# mkii.net
KiCad netlist of a schematic drawn in EAGLE
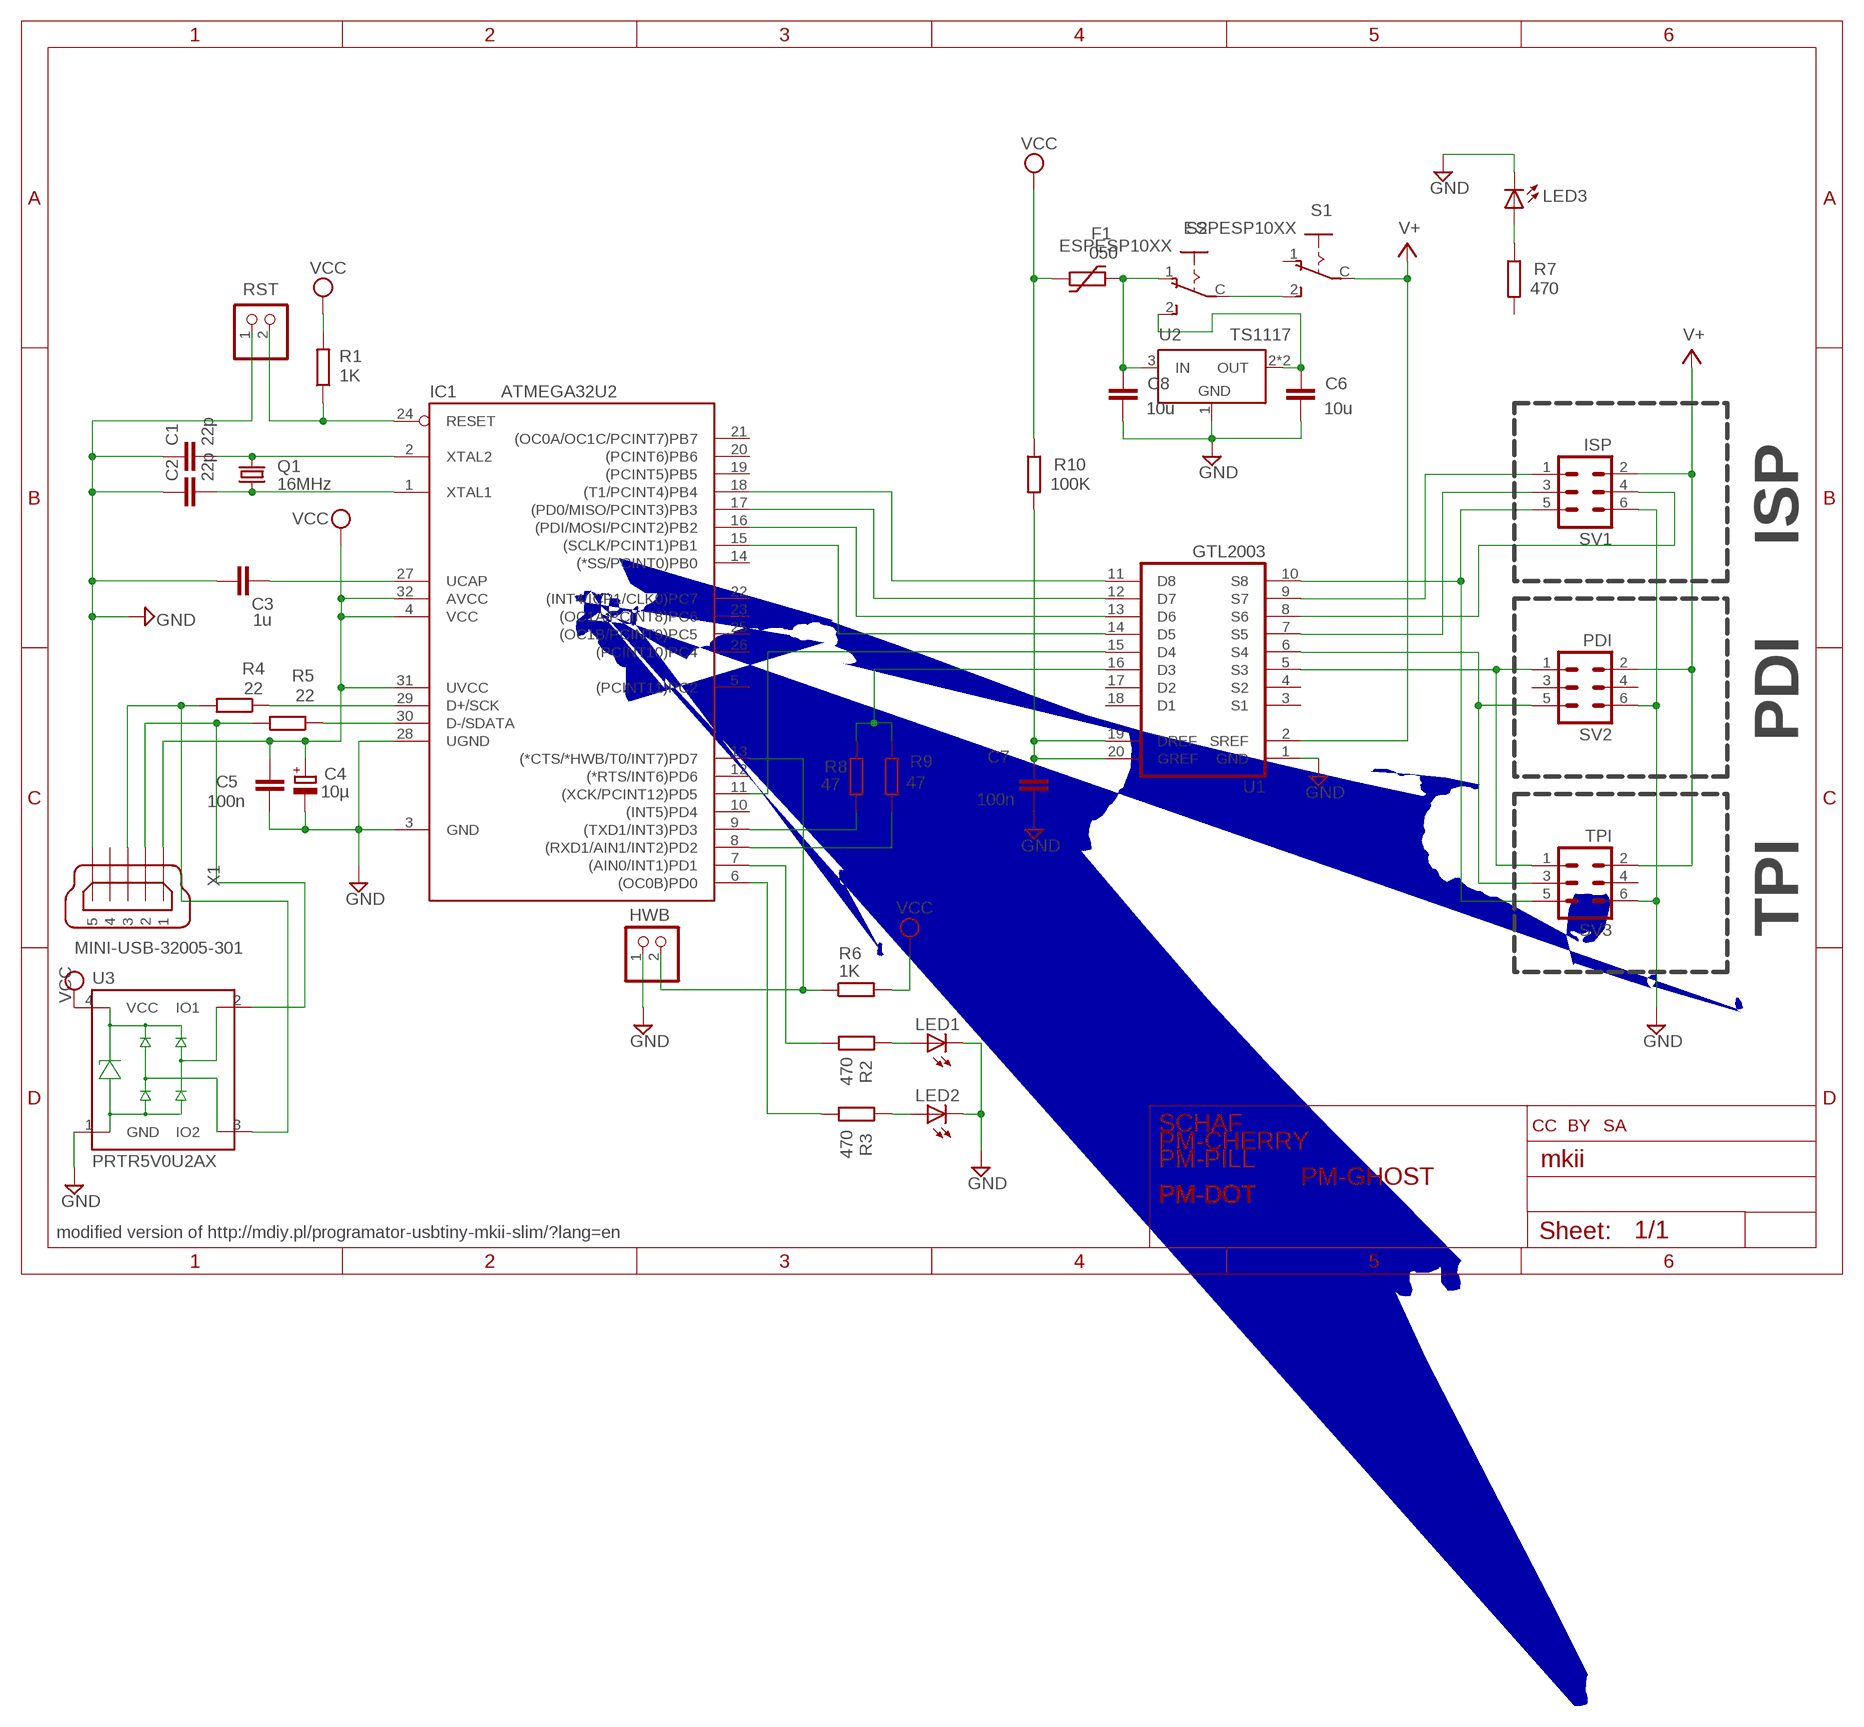
[diagram p0: schematic, sheet 1]

(export (version "E")
  (design (tool "Eeschema 10.0.6"))
  (components
    (comp (ref "C1")
      (value "22p")
      (footprint "eagle-import:C0603")
      (libsource (lib "eagle-import") (part "C-EUC0603"))
    )
    (comp (ref "C2")
      (value "22p")
      (footprint "eagle-import:C0603")
      (libsource (lib "eagle-import") (part "C-EUC0603"))
    )
    (comp (ref "C3")
      (value "1u")
      (footprint "eagle-import:C0805")
      (libsource (lib "eagle-import") (part "C-EUC0805"))
    )
    (comp (ref "C4")
      (value "10µ")
      (footprint "eagle-import:153CLV-0505")
      (libsource (lib "eagle-import") (part "CPOL-EU153CLV-0505"))
    )
    (comp (ref "C5")
      (value "100n")
      (footprint "eagle-import:C0603")
      (libsource (lib "eagle-import") (part "C-EUC0603"))
    )
    (comp (ref "C6")
      (value "10u")
      (footprint "eagle-import:C0805")
      (libsource (lib "eagle-import") (part "C-EUC0805"))
    )
    (comp (ref "C7")
      (value "100n")
      (footprint "eagle-import:C0603")
      (libsource (lib "eagle-import") (part "C-EUC0603"))
    )
    (comp (ref "C8")
      (value "10u")
      (footprint "eagle-import:C0805")
      (libsource (lib "eagle-import") (part "C-EUC0805"))
    )
    (comp (ref "F1")
      (value "050")
      (footprint "eagle-import:1812L")
      (libsource (lib "eagle-import") (part "1812L"))
    )
    (comp (ref "HWB")
      (value "PINHD-1X02_2.54-S")
      (footprint "eagle-import:1X02-S")
      (libsource (lib "eagle-import") (part "PINHD-1X02_2.54-S"))
    )
    (comp (ref "IC1")
      (value "ATMEGA32U2")
      (footprint "eagle-import:TQFP32-08")
      (libsource (lib "eagle-import") (part "AT90USB162-AU"))
    )
    (comp (ref "LED1")
      (value "LEDCHIP-LED0603")
      (footprint "eagle-import:CHIP-LED0603")
      (libsource (lib "eagle-import") (part "LEDCHIP-LED0603"))
    )
    (comp (ref "LED2")
      (value "LEDCHIP-LED0603")
      (footprint "eagle-import:CHIP-LED0603")
      (libsource (lib "eagle-import") (part "LEDCHIP-LED0603"))
    )
    (comp (ref "LED3")
      (value "LEDCHIP-LED0603")
      (footprint "eagle-import:CHIP-LED0603")
      (libsource (lib "eagle-import") (part "LEDCHIP-LED0603"))
    )
    (comp (ref "Q1")
      (value "16MHz")
      (footprint "eagle-import:HC49_S")
      (libsource (lib "eagle-import") (part "CRYSTALHC49S"))
    )
    (comp (ref "R1")
      (value "1K")
      (footprint "eagle-import:R0603")
      (libsource (lib "eagle-import") (part "R-EU_R0603"))
    )
    (comp (ref "R2")
      (value "470")
      (footprint "eagle-import:R0603")
      (libsource (lib "eagle-import") (part "R-EU_R0603"))
    )
    (comp (ref "R3")
      (value "470")
      (footprint "eagle-import:R0603")
      (libsource (lib "eagle-import") (part "R-EU_R0603"))
    )
    (comp (ref "R4")
      (value "22")
      (footprint "eagle-import:R0603")
      (libsource (lib "eagle-import") (part "R-EU_R0603"))
    )
    (comp (ref "R5")
      (value "22")
      (footprint "eagle-import:R0603")
      (libsource (lib "eagle-import") (part "R-EU_R0603"))
    )
    (comp (ref "R6")
      (value "1K")
      (footprint "eagle-import:R0603")
      (libsource (lib "eagle-import") (part "R-EU_R0603"))
    )
    (comp (ref "R7")
      (value "470")
      (footprint "eagle-import:R0603")
      (libsource (lib "eagle-import") (part "R-EU_R0603"))
    )
    (comp (ref "R8")
      (value "47")
      (footprint "eagle-import:R0603")
      (libsource (lib "eagle-import") (part "R-EU_R0603"))
    )
    (comp (ref "R9")
      (value "47")
      (footprint "eagle-import:R0603")
      (libsource (lib "eagle-import") (part "R-EU_R0603"))
    )
    (comp (ref "R10")
      (value "100K")
      (footprint "eagle-import:R0603")
      (libsource (lib "eagle-import") (part "R-EU_R0603"))
    )
    (comp (ref "RST")
      (value "PINHD-1X02_2.54-S")
      (footprint "eagle-import:1X02-S")
      (libsource (lib "eagle-import") (part "PINHD-1X02_2.54-S"))
    )
    (comp (ref "S1")
      (value "ESPESP10XX")
      (footprint "eagle-import:ESP10XX")
      (libsource (lib "eagle-import") (part "ESPESP10XX"))
    )
    (comp (ref "S2")
      (value "ESPESP10XX")
      (footprint "eagle-import:ESP10XX")
      (libsource (lib "eagle-import") (part "ESPESP10XX"))
    )
    (comp (ref "SV1")
      (value "ISP")
      (footprint "eagle-import:ML6")
      (libsource (lib "eagle-import") (part "ML6"))
    )
    (comp (ref "SV2")
      (value "PDI")
      (footprint "eagle-import:ML6")
      (libsource (lib "eagle-import") (part "ML6"))
    )
    (comp (ref "SV3")
      (value "TPI")
      (footprint "eagle-import:ML6")
      (libsource (lib "eagle-import") (part "ML6"))
    )
    (comp (ref "U$1")
      (value "CC-TPLACE-HALF")
      (footprint "eagle-import:CC_TPLACE_HS")
      (libsource (lib "eagle-import") (part "CC-TPLACE-HALF"))
    )
    (comp (ref "U$2")
      (value "BY-TPLACE-HS")
      (footprint "eagle-import:BY_TPLACE_HS")
      (libsource (lib "eagle-import") (part "BY-TPLACE-HS"))
    )
    (comp (ref "U$3")
      (value "SA-TPLACE-HALF")
      (footprint "eagle-import:SA_TPLACE_HS")
      (libsource (lib "eagle-import") (part "SA-TPLACE-HALF"))
    )
    (comp (ref "U$4")
      (value "SCHAF7MM")
      (footprint "eagle-import:SCHAF-7")
      (libsource (lib "eagle-import") (part "SCHAF7MM"))
    )
    (comp (ref "U$5")
      (value "PM-CHERRY5")
      (footprint "eagle-import:PM-CHERRY-5")
      (libsource (lib "eagle-import") (part "PM-CHERRY5"))
    )
    (comp (ref "U$6")
      (value "PM-PILL5")
      (footprint "eagle-import:PM-PILL-5")
      (libsource (lib "eagle-import") (part "PM-PILL5"))
    )
    (comp (ref "U$8")
      (value "PM-DOT5")
      (footprint "eagle-import:PM-DOT5")
      (libsource (lib "eagle-import") (part "PM-DOT5"))
    )
    (comp (ref "U$9")
      (value "PM-DOT5")
      (footprint "eagle-import:PM-DOT5")
      (libsource (lib "eagle-import") (part "PM-DOT5"))
    )
    (comp (ref "U$10")
      (value "PM-DOT5")
      (footprint "eagle-import:PM-DOT5")
      (libsource (lib "eagle-import") (part "PM-DOT5"))
    )
    (comp (ref "U$11")
      (value "PM-DOT5")
      (footprint "eagle-import:PM-DOT5")
      (libsource (lib "eagle-import") (part "PM-DOT5"))
    )
    (comp (ref "U$12")
      (value "PM-DOT5")
      (footprint "eagle-import:PM-DOT5")
      (libsource (lib "eagle-import") (part "PM-DOT5"))
    )
    (comp (ref "U$13")
      (value "PM-DOT5")
      (footprint "eagle-import:PM-DOT5")
      (libsource (lib "eagle-import") (part "PM-DOT5"))
    )
    (comp (ref "U$14")
      (value "PM-DOT5")
      (footprint "eagle-import:PM-DOT5")
      (libsource (lib "eagle-import") (part "PM-DOT5"))
    )
    (comp (ref "U$15")
      (value "PM-DOT5")
      (footprint "eagle-import:PM-DOT5")
      (libsource (lib "eagle-import") (part "PM-DOT5"))
    )
    (comp (ref "U$16")
      (value "PM-GHOSTA5")
      (footprint "eagle-import:PM-GHOSTA-5")
      (libsource (lib "eagle-import") (part "PM-GHOSTA5"))
    )
    (comp (ref "U1")
      (value "GTL2003")
      (footprint "eagle-import:TSSOP20")
      (libsource (lib "eagle-import") (part "GTL2003"))
    )
    (comp (ref "U2")
      (value "TS1117")
      (footprint "eagle-import:SOT223")
      (libsource (lib "eagle-import") (part "TS1117"))
    )
    (comp (ref "U3")
      (value "PRTR5V0U2AX")
      (footprint "eagle-import:SOT143B")
      (libsource (lib "eagle-import") (part "PRTR5V0U2AX"))
    )
    (comp (ref "X1")
      (value "MINI-USB-32005-301")
      (footprint "eagle-import:32005-301")
      (libsource (lib "eagle-import") (part "MINI-USB-32005-301"))
    )
  )
  (nets
    (net (code "1") (name "GND") (class "Default")
      (node (ref "C1") (pin "1") (pinfunction "1_1") (pintype "passive"))
      (node (ref "C2") (pin "1") (pinfunction "1_1") (pintype "passive"))
      (node (ref "C3") (pin "1") (pinfunction "1_1") (pintype "passive"))
      (node (ref "C4") (pin "-") (pinfunction "-_-") (pintype "passive"))
      (node (ref "C5") (pin "1") (pinfunction "1_1") (pintype "passive"))
      (node (ref "C6") (pin "1") (pinfunction "1_1") (pintype "passive"))
      (node (ref "C7") (pin "1") (pinfunction "1_1") (pintype "passive"))
      (node (ref "C8") (pin "1") (pinfunction "1_1") (pintype "passive"))
      (node (ref "HWB") (pin "1") (pinfunction "1_1") (pintype "passive"))
      (node (ref "IC1") (pin "28") (pinfunction "UGND_28") (pintype "power_in"))
      (node (ref "IC1") (pin "3") (pinfunction "GND_3") (pintype "power_in"))
      (node (ref "LED1") (pin "C") (pinfunction "C_C") (pintype "passive"))
      (node (ref "LED2") (pin "C") (pinfunction "C_C") (pintype "passive"))
      (node (ref "LED3") (pin "C") (pinfunction "C_C") (pintype "passive"))
      (node (ref "RST") (pin "1") (pinfunction "1_1") (pintype "passive"))
      (node (ref "SV1") (pin "6") (pinfunction "6_6") (pintype "passive"))
      (node (ref "SV2") (pin "6") (pinfunction "6_6") (pintype "passive"))
      (node (ref "SV3") (pin "6") (pinfunction "6_6") (pintype "passive"))
      (node (ref "U1") (pin "1") (pinfunction "GND_1") (pintype "power_in"))
      (node (ref "U2") (pin "1") (pinfunction "GND_1") (pintype "power_in"))
      (node (ref "U3") (pin "1") (pinfunction "GND_1") (pintype "power_in"))
      (node (ref "X1") (pin "5") (pinfunction "5_5") (pintype "passive"))
    )
    (net (code "2") (name "Net-(F1-2)") (class "Default")
      (node (ref "C8") (pin "2") (pinfunction "2_2") (pintype "passive"))
      (node (ref "F1") (pin "P$2") (pinfunction "2_P$2") (pintype "passive"))
      (node (ref "S2") (pin "1") (pinfunction "O_1") (pintype "passive"))
      (node (ref "U2") (pin "3") (pinfunction "IN_3") (pintype "input"))
    )
    (net (code "3") (name "Net-(IC1-(*CTS{slash}*HWB{slash}T0{slash}INT7)PD7)") (class "Default")
      (node (ref "HWB") (pin "2") (pinfunction "2_2") (pintype "passive"))
      (node (ref "IC1") (pin "13") (pinfunction "(*CTS/*HWB/T0/INT7)PD7_13") (pintype "bidirectional"))
      (node (ref "R6") (pin "1") (pinfunction "1_1") (pintype "passive"))
    )
    (net (code "4") (name "Net-(IC1-(AIN0{slash}INT1)PD1)") (class "Default")
      (node (ref "IC1") (pin "7") (pinfunction "(AIN0/INT1)PD1_7") (pintype "bidirectional"))
      (node (ref "R2") (pin "2") (pinfunction "2_2") (pintype "passive"))
    )
    (net (code "5") (name "Net-(IC1-(OC0B)PD0)") (class "Default")
      (node (ref "IC1") (pin "6") (pinfunction "(OC0B)PD0_6") (pintype "bidirectional"))
      (node (ref "R3") (pin "2") (pinfunction "2_2") (pintype "passive"))
    )
    (net (code "6") (name "Net-(IC1-(PD0{slash}MISO{slash}PCINT3)PB3)") (class "Default")
      (node (ref "IC1") (pin "17") (pinfunction "(PD0/MISO/PCINT3)PB3_17") (pintype "bidirectional"))
      (node (ref "U1") (pin "12") (pinfunction "D7_12") (pintype "bidirectional"))
    )
    (net (code "7") (name "Net-(IC1-(PDI{slash}MOSI{slash}PCINT2)PB2)") (class "Default")
      (node (ref "IC1") (pin "16") (pinfunction "(PDI/MOSI/PCINT2)PB2_16") (pintype "bidirectional"))
      (node (ref "U1") (pin "13") (pinfunction "D6_13") (pintype "bidirectional"))
    )
    (net (code "8") (name "Net-(IC1-(RXD1{slash}AIN1{slash}INT2)PD2)") (class "Default")
      (node (ref "IC1") (pin "8") (pinfunction "(RXD1/AIN1/INT2)PD2_8") (pintype "bidirectional"))
      (node (ref "R9") (pin "2") (pinfunction "2_2") (pintype "passive"))
    )
    (net (code "9") (name "Net-(IC1-(SCLK{slash}PCINT1)PB1)") (class "Default")
      (node (ref "IC1") (pin "15") (pinfunction "(SCLK/PCINT1)PB1_15") (pintype "bidirectional"))
      (node (ref "U1") (pin "14") (pinfunction "D5_14") (pintype "bidirectional"))
    )
    (net (code "10") (name "Net-(IC1-(T1{slash}PCINT4)PB4)") (class "Default")
      (node (ref "IC1") (pin "18") (pinfunction "(T1/PCINT4)PB4_18") (pintype "bidirectional"))
      (node (ref "U1") (pin "11") (pinfunction "D8_11") (pintype "bidirectional"))
    )
    (net (code "11") (name "Net-(IC1-(TXD1{slash}INT3)PD3)") (class "Default")
      (node (ref "IC1") (pin "9") (pinfunction "(TXD1/INT3)PD3_9") (pintype "bidirectional"))
      (node (ref "R8") (pin "2") (pinfunction "2_2") (pintype "passive"))
    )
    (net (code "12") (name "Net-(IC1-(XCK{slash}PCINT12)PD5)") (class "Default")
      (node (ref "IC1") (pin "11") (pinfunction "(XCK/PCINT12)PD5_11") (pintype "bidirectional"))
      (node (ref "U1") (pin "15") (pinfunction "D4_15") (pintype "bidirectional"))
    )
    (net (code "13") (name "Net-(IC1-D+{slash}SCK)") (class "Default")
      (node (ref "IC1") (pin "29") (pinfunction "D+/SCK_29") (pintype "bidirectional"))
      (node (ref "R4") (pin "1") (pinfunction "1_1") (pintype "passive"))
    )
    (net (code "14") (name "Net-(IC1-D-{slash}SDATA)") (class "Default")
      (node (ref "IC1") (pin "30") (pinfunction "D-/SDATA_30") (pintype "bidirectional"))
      (node (ref "R5") (pin "1") (pinfunction "1_1") (pintype "passive"))
    )
    (net (code "15") (name "Net-(IC1-RESET)") (class "Default")
      (node (ref "IC1") (pin "24") (pinfunction "RESET_24") (pintype "input"))
      (node (ref "R1") (pin "1") (pinfunction "1_1") (pintype "passive"))
      (node (ref "RST") (pin "2") (pinfunction "2_2") (pintype "passive"))
    )
    (net (code "16") (name "Net-(IC1-UCAP)") (class "Default")
      (node (ref "C3") (pin "2") (pinfunction "2_2") (pintype "passive"))
      (node (ref "IC1") (pin "27") (pinfunction "UCAP_27") (pintype "power_in"))
    )
    (net (code "17") (name "Net-(IC1-XTAL1)") (class "Default")
      (node (ref "C2") (pin "2") (pinfunction "2_2") (pintype "passive"))
      (node (ref "IC1") (pin "1") (pinfunction "XTAL1_1") (pintype "bidirectional"))
      (node (ref "Q1") (pin "1") (pinfunction "1_1") (pintype "passive"))
    )
    (net (code "18") (name "Net-(IC1-XTAL2)") (class "Default")
      (node (ref "C1") (pin "2") (pinfunction "2_2") (pintype "passive"))
      (node (ref "IC1") (pin "2") (pinfunction "XTAL2_2") (pintype "bidirectional"))
      (node (ref "Q1") (pin "2") (pinfunction "2_2") (pintype "passive"))
    )
    (net (code "19") (name "Net-(LED1-PadA)") (class "Default")
      (node (ref "LED1") (pin "A") (pinfunction "A_A") (pintype "passive"))
      (node (ref "R2") (pin "1") (pinfunction "1_1") (pintype "passive"))
    )
    (net (code "20") (name "Net-(LED2-PadA)") (class "Default")
      (node (ref "LED2") (pin "A") (pinfunction "A_A") (pintype "passive"))
      (node (ref "R3") (pin "1") (pinfunction "1_1") (pintype "passive"))
    )
    (net (code "21") (name "Net-(LED3-PadA)") (class "Default")
      (node (ref "LED3") (pin "A") (pinfunction "A_A") (pintype "passive"))
      (node (ref "R7") (pin "1") (pinfunction "1_1") (pintype "passive"))
    )
    (net (code "22") (name "Net-(S1-S)") (class "Default")
      (node (ref "S1") (pin "2") (pinfunction "S_2") (pintype "passive"))
      (node (ref "S2") (pin "C") (pinfunction "P_C") (pintype "passive"))
    )
    (net (code "23") (name "Net-(S2-S)") (class "Default")
      (node (ref "C6") (pin "2") (pinfunction "2_2") (pintype "passive"))
      (node (ref "S2") (pin "2") (pinfunction "S_2") (pintype "passive"))
      (node (ref "U2") (pin "2") (pinfunction "OUT_2") (pintype "output"))
      (node (ref "U2") (pin "4") (pinfunction "OUT_4") (pintype "output"))
    )
    (net (code "24") (name "Net-(U1-D3)") (class "Default")
      (node (ref "R8") (pin "1") (pinfunction "1_1") (pintype "passive"))
      (node (ref "R9") (pin "1") (pinfunction "1_1") (pintype "passive"))
      (node (ref "U1") (pin "16") (pinfunction "D3_16") (pintype "bidirectional"))
    )
    (net (code "25") (name "Net-(U1-DREF)") (class "Default")
      (node (ref "C7") (pin "2") (pinfunction "2_2") (pintype "passive"))
      (node (ref "R10") (pin "2") (pinfunction "2_2") (pintype "passive"))
      (node (ref "U1") (pin "19") (pinfunction "DREF_19") (pintype "bidirectional"))
      (node (ref "U1") (pin "20") (pinfunction "GREF_20") (pintype "bidirectional"))
    )
    (net (code "26") (name "Net-(U1-S3)") (class "Default")
      (node (ref "SV2") (pin "1") (pinfunction "1_1") (pintype "passive"))
      (node (ref "SV3") (pin "1") (pinfunction "1_1") (pintype "passive"))
      (node (ref "U1") (pin "5") (pinfunction "S3_5") (pintype "bidirectional"))
    )
    (net (code "27") (name "Net-(U1-S4)") (class "Default")
      (node (ref "SV2") (pin "5") (pinfunction "5_5") (pintype "passive"))
      (node (ref "SV3") (pin "3") (pinfunction "3_3") (pintype "passive"))
      (node (ref "U1") (pin "6") (pinfunction "S4_6") (pintype "bidirectional"))
    )
    (net (code "28") (name "Net-(U1-S5)") (class "Default")
      (node (ref "SV1") (pin "3") (pinfunction "3_3") (pintype "passive"))
      (node (ref "U1") (pin "7") (pinfunction "S5_7") (pintype "bidirectional"))
    )
    (net (code "29") (name "Net-(U1-S6)") (class "Default")
      (node (ref "SV1") (pin "4") (pinfunction "4_4") (pintype "passive"))
      (node (ref "U1") (pin "8") (pinfunction "S6_8") (pintype "bidirectional"))
    )
    (net (code "30") (name "Net-(U1-S7)") (class "Default")
      (node (ref "SV1") (pin "1") (pinfunction "1_1") (pintype "passive"))
      (node (ref "U1") (pin "9") (pinfunction "S7_9") (pintype "bidirectional"))
    )
    (net (code "31") (name "Net-(U1-S8)") (class "Default")
      (node (ref "SV1") (pin "5") (pinfunction "5_5") (pintype "passive"))
      (node (ref "SV3") (pin "5") (pinfunction "5_5") (pintype "passive"))
      (node (ref "U1") (pin "10") (pinfunction "S8_10") (pintype "bidirectional"))
    )
    (net (code "32") (name "Net-(U3-IO1)") (class "Default")
      (node (ref "R5") (pin "2") (pinfunction "2_2") (pintype "passive"))
      (node (ref "U3") (pin "2") (pinfunction "IO1_2") (pintype "bidirectional"))
      (node (ref "X1") (pin "2") (pinfunction "2_2") (pintype "passive"))
    )
    (net (code "33") (name "Net-(U3-IO2)") (class "Default")
      (node (ref "R4") (pin "2") (pinfunction "2_2") (pintype "passive"))
      (node (ref "U3") (pin "3") (pinfunction "IO2_3") (pintype "bidirectional"))
      (node (ref "X1") (pin "3") (pinfunction "3_3") (pintype "passive"))
    )
    (net (code "34") (name "V+") (class "Default")
      (node (ref "S1") (pin "C") (pinfunction "P_C") (pintype "passive"))
      (node (ref "SV1") (pin "2") (pinfunction "2_2") (pintype "passive"))
      (node (ref "SV2") (pin "2") (pinfunction "2_2") (pintype "passive"))
      (node (ref "SV3") (pin "2") (pinfunction "2_2") (pintype "passive"))
      (node (ref "U1") (pin "2") (pinfunction "SREF_2") (pintype "bidirectional"))
    )
    (net (code "35") (name "VCC") (class "Default")
      (node (ref "C4") (pin "+") (pinfunction "+_+") (pintype "passive"))
      (node (ref "C5") (pin "2") (pinfunction "2_2") (pintype "passive"))
      (node (ref "F1") (pin "P$1") (pinfunction "1_P$1") (pintype "passive"))
      (node (ref "IC1") (pin "31") (pinfunction "UVCC_31") (pintype "power_in"))
      (node (ref "IC1") (pin "32") (pinfunction "AVCC_32") (pintype "power_in"))
      (node (ref "IC1") (pin "4") (pinfunction "VCC_4") (pintype "power_in"))
      (node (ref "R1") (pin "2") (pinfunction "2_2") (pintype "passive"))
      (node (ref "R10") (pin "1") (pinfunction "1_1") (pintype "passive"))
      (node (ref "R6") (pin "2") (pinfunction "2_2") (pintype "passive"))
      (node (ref "U3") (pin "4") (pinfunction "VCC_4") (pintype "power_in"))
      (node (ref "X1") (pin "1") (pinfunction "1_1") (pintype "passive"))
    )
    (net (code "36") (name "unconnected-(IC1-(*RTS{slash}INT6)PD6-Pad12)") (class "Default")
      (node (ref "IC1") (pin "12") (pinfunction "(*RTS/INT6)PD6_12") (pintype "bidirectional"))
    )
    (net (code "37") (name "unconnected-(IC1-(*SS{slash}PCINT0)PB0-Pad14)") (class "Default")
      (node (ref "IC1") (pin "14") (pinfunction "(*SS/PCINT0)PB0_14") (pintype "bidirectional"))
    )
    (net (code "38") (name "unconnected-(IC1-(INT4{slash}ICP1{slash}CLK0)PC7-Pad22)") (class "Default")
      (node (ref "IC1") (pin "22") (pinfunction "(INT4/ICP1/CLK0)PC7_22") (pintype "bidirectional"))
    )
    (net (code "39") (name "unconnected-(IC1-(INT5)PD4-Pad10)") (class "Default")
      (node (ref "IC1") (pin "10") (pinfunction "(INT5)PD4_10") (pintype "bidirectional"))
    )
    (net (code "40") (name "unconnected-(IC1-(OC0A{slash}OC1C{slash}PCINT7)PB7-Pad21)") (class "Default")
      (node (ref "IC1") (pin "21") (pinfunction "(OC0A/OC1C/PCINT7)PB7_21") (pintype "bidirectional"))
    )
    (net (code "41") (name "unconnected-(IC1-(OC1A{slash}PCINT8)PC6-Pad23)") (class "Default")
      (node (ref "IC1") (pin "23") (pinfunction "(OC1A/PCINT8)PC6_23") (pintype "bidirectional"))
    )
    (net (code "42") (name "unconnected-(IC1-(OC1B{slash}PCINT9)PC5-Pad25)") (class "Default")
      (node (ref "IC1") (pin "25") (pinfunction "(OC1B/PCINT9)PC5_25") (pintype "bidirectional"))
    )
    (net (code "43") (name "unconnected-(IC1-(PCINT5)PB5-Pad19)") (class "Default")
      (node (ref "IC1") (pin "19") (pinfunction "(PCINT5)PB5_19") (pintype "bidirectional"))
    )
    (net (code "44") (name "unconnected-(IC1-(PCINT6)PB6-Pad20)") (class "Default")
      (node (ref "IC1") (pin "20") (pinfunction "(PCINT6)PB6_20") (pintype "bidirectional"))
    )
    (net (code "45") (name "unconnected-(IC1-(PCINT10)PC4-Pad26)") (class "Default")
      (node (ref "IC1") (pin "26") (pinfunction "(PCINT10)PC4_26") (pintype "bidirectional"))
    )
    (net (code "46") (name "unconnected-(IC1-(PCINT11)PC2-Pad5)") (class "Default")
      (node (ref "IC1") (pin "5") (pinfunction "(PCINT11)PC2_5") (pintype "bidirectional"))
    )
    (net (code "47") (name "unconnected-(R7-Pad2)") (class "Default")
      (node (ref "R7") (pin "2") (pinfunction "2_2") (pintype "passive"))
    )
    (net (code "48") (name "unconnected-(S1-O-Pad1)") (class "Default")
      (node (ref "S1") (pin "1") (pinfunction "O_1") (pintype "passive"))
    )
    (net (code "49") (name "unconnected-(SV2-Pad3)") (class "Default")
      (node (ref "SV2") (pin "3") (pinfunction "3_3") (pintype "passive"))
    )
    (net (code "50") (name "unconnected-(SV2-Pad4)") (class "Default")
      (node (ref "SV2") (pin "4") (pinfunction "4_4") (pintype "passive"))
    )
    (net (code "51") (name "unconnected-(SV3-Pad4)") (class "Default")
      (node (ref "SV3") (pin "4") (pinfunction "4_4") (pintype "passive"))
    )
    (net (code "52") (name "unconnected-(U1-D1-Pad18)") (class "Default")
      (node (ref "U1") (pin "18") (pinfunction "D1_18") (pintype "bidirectional"))
    )
    (net (code "53") (name "unconnected-(U1-D2-Pad17)") (class "Default")
      (node (ref "U1") (pin "17") (pinfunction "D2_17") (pintype "bidirectional"))
    )
    (net (code "54") (name "unconnected-(U1-S1-Pad3)") (class "Default")
      (node (ref "U1") (pin "3") (pinfunction "S1_3") (pintype "bidirectional"))
    )
    (net (code "55") (name "unconnected-(U1-S2-Pad4)") (class "Default")
      (node (ref "U1") (pin "4") (pinfunction "S2_4") (pintype "bidirectional"))
    )
    (net (code "56") (name "unconnected-(X1-Pad4)") (class "Default")
      (node (ref "X1") (pin "4") (pinfunction "4_4") (pintype "passive"))
    )
  )
)
